# DoDecaCharlieCylon.net
KiCad netlist of a schematic drawn in EAGLE
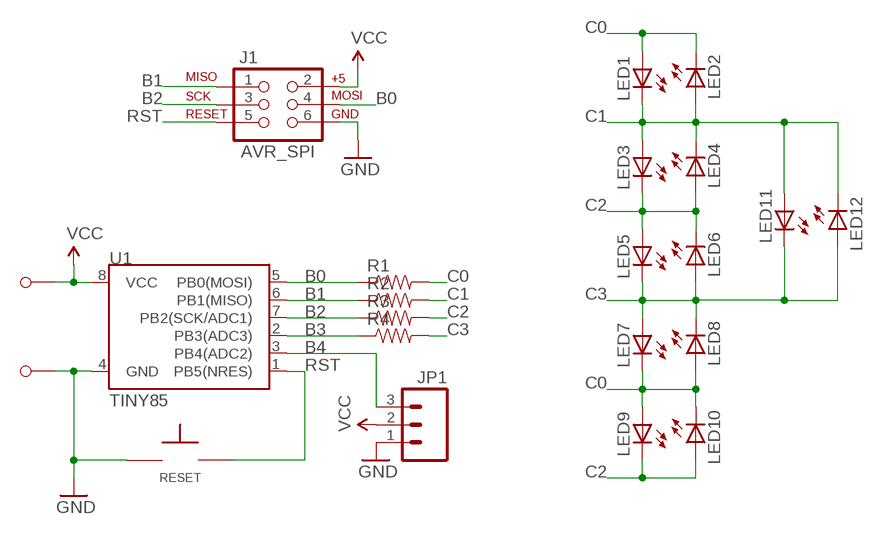
[diagram p0: schematic, sheet 1]

(export (version "E")
  (design (tool "Eeschema 10.0.6"))
  (components
    (comp (ref "J1")
      (value "AVR_SPI")
      (footprint "eagle-import:2X3-NS")
      (libsource (lib "eagle-import") (part "AVR_SPI_PRG_6LABELED"))
    )
    (comp (ref "JP1")
      (value "M03PTH")
      (footprint "eagle-import:1X03")
      (libsource (lib "eagle-import") (part "M03PTH"))
    )
    (comp (ref "LED1")
      (value "LEDOVAL")
      (footprint "eagle-import:LED-OVAL")
      (libsource (lib "eagle-import") (part "LEDOVAL"))
    )
    (comp (ref "LED2")
      (value "LEDOVAL")
      (footprint "eagle-import:LED-OVAL")
      (libsource (lib "eagle-import") (part "LEDOVAL"))
    )
    (comp (ref "LED3")
      (value "LEDOVAL")
      (footprint "eagle-import:LED-OVAL")
      (libsource (lib "eagle-import") (part "LEDOVAL"))
    )
    (comp (ref "LED4")
      (value "LEDOVAL")
      (footprint "eagle-import:LED-OVAL")
      (libsource (lib "eagle-import") (part "LEDOVAL"))
    )
    (comp (ref "LED5")
      (value "LEDOVAL")
      (footprint "eagle-import:LED-OVAL")
      (libsource (lib "eagle-import") (part "LEDOVAL"))
    )
    (comp (ref "LED6")
      (value "LEDOVAL")
      (footprint "eagle-import:LED-OVAL")
      (libsource (lib "eagle-import") (part "LEDOVAL"))
    )
    (comp (ref "LED7")
      (value "LEDOVAL")
      (footprint "eagle-import:LED-OVAL")
      (libsource (lib "eagle-import") (part "LEDOVAL"))
    )
    (comp (ref "LED8")
      (value "LEDOVAL")
      (footprint "eagle-import:LED-OVAL")
      (libsource (lib "eagle-import") (part "LEDOVAL"))
    )
    (comp (ref "LED9")
      (value "LEDOVAL")
      (footprint "eagle-import:LED-OVAL")
      (libsource (lib "eagle-import") (part "LEDOVAL"))
    )
    (comp (ref "LED10")
      (value "LEDOVAL")
      (footprint "eagle-import:LED-OVAL")
      (libsource (lib "eagle-import") (part "LEDOVAL"))
    )
    (comp (ref "LED11")
      (value "LEDOVAL")
      (footprint "eagle-import:LED-OVAL")
      (libsource (lib "eagle-import") (part "LEDOVAL"))
    )
    (comp (ref "LED12")
      (value "LEDOVAL")
      (footprint "eagle-import:LED-OVAL")
      (libsource (lib "eagle-import") (part "LEDOVAL"))
    )
    (comp (ref "R1")
      (value "RESISTORAXIAL-0.3")
      (footprint "eagle-import:AXIAL-0.3")
      (libsource (lib "eagle-import") (part "RESISTORAXIAL-0.3"))
    )
    (comp (ref "R2")
      (value "RESISTORAXIAL-0.3")
      (footprint "eagle-import:AXIAL-0.3")
      (libsource (lib "eagle-import") (part "RESISTORAXIAL-0.3"))
    )
    (comp (ref "R3")
      (value "RESISTORAXIAL-0.3")
      (footprint "eagle-import:AXIAL-0.3")
      (libsource (lib "eagle-import") (part "RESISTORAXIAL-0.3"))
    )
    (comp (ref "R4")
      (value "RESISTORAXIAL-0.3")
      (footprint "eagle-import:AXIAL-0.3")
      (libsource (lib "eagle-import") (part "RESISTORAXIAL-0.3"))
    )
    (comp (ref "RESET")
      (value "TAC_SPST_NO")
      (footprint "eagle-import:TAC_SPST_NO")
      (libsource (lib "eagle-import") (part "TAC_SPST_NO"))
    )
    (comp (ref "U$1")
      (value "M1")
      (footprint "eagle-import:M1_NO_STRAIN")
      (libsource (lib "eagle-import") (part "M1"))
    )
    (comp (ref "U$2")
      (value "M1")
      (footprint "eagle-import:M1_NO_STRAIN")
      (libsource (lib "eagle-import") (part "M1"))
    )
    (comp (ref "U1")
      (value "TINY85")
      (footprint "eagle-import:DIP08")
      (libsource (lib "eagle-import") (part "ATTINY45TINY85-20-DIP"))
    )
  )
  (nets
    (net (code "1") (name "/B0") (class "Default")
      (node (ref "J1") (pin "4") (pinfunction "MOSI_4") (pintype "passive"))
      (node (ref "R1") (pin "P$1") (pinfunction "1_P$1") (pintype "passive"))
      (node (ref "U1") (pin "5") (pinfunction "PB0(MOSI)_5") (pintype "bidirectional"))
    )
    (net (code "2") (name "/B1") (class "Default")
      (node (ref "J1") (pin "1") (pinfunction "MISO_1") (pintype "passive"))
      (node (ref "R2") (pin "P$1") (pinfunction "1_P$1") (pintype "passive"))
      (node (ref "U1") (pin "6") (pinfunction "PB1(MISO)_6") (pintype "bidirectional"))
    )
    (net (code "3") (name "/B2") (class "Default")
      (node (ref "J1") (pin "3") (pinfunction "SCK_3") (pintype "passive"))
      (node (ref "R3") (pin "P$1") (pinfunction "1_P$1") (pintype "passive"))
      (node (ref "U1") (pin "7") (pinfunction "PB2(SCK/ADC1)_7") (pintype "bidirectional"))
    )
    (net (code "4") (name "/B3") (class "Default")
      (node (ref "R4") (pin "P$1") (pinfunction "1_P$1") (pintype "passive"))
      (node (ref "U1") (pin "2") (pinfunction "PB3(ADC3)_2") (pintype "bidirectional"))
    )
    (net (code "5") (name "/B4") (class "Default")
      (node (ref "JP1") (pin "3") (pinfunction "3_3") (pintype "passive"))
      (node (ref "U1") (pin "3") (pinfunction "PB4(ADC2)_3") (pintype "bidirectional"))
    )
    (net (code "6") (name "/C0") (class "Default")
      (node (ref "LED1") (pin "ANODE") (pinfunction "A_ANODE") (pintype "passive"))
      (node (ref "LED10") (pin "CATHODE") (pinfunction "C_CATHODE") (pintype "passive"))
      (node (ref "LED2") (pin "CATHODE") (pinfunction "C_CATHODE") (pintype "passive"))
      (node (ref "LED7") (pin "CATHODE") (pinfunction "C_CATHODE") (pintype "passive"))
      (node (ref "LED8") (pin "ANODE") (pinfunction "A_ANODE") (pintype "passive"))
      (node (ref "LED9") (pin "ANODE") (pinfunction "A_ANODE") (pintype "passive"))
      (node (ref "R1") (pin "P$2") (pinfunction "2_P$2") (pintype "passive"))
    )
    (net (code "7") (name "/C1") (class "Default")
      (node (ref "LED1") (pin "CATHODE") (pinfunction "C_CATHODE") (pintype "passive"))
      (node (ref "LED11") (pin "ANODE") (pinfunction "A_ANODE") (pintype "passive"))
      (node (ref "LED12") (pin "CATHODE") (pinfunction "C_CATHODE") (pintype "passive"))
      (node (ref "LED2") (pin "ANODE") (pinfunction "A_ANODE") (pintype "passive"))
      (node (ref "LED3") (pin "ANODE") (pinfunction "A_ANODE") (pintype "passive"))
      (node (ref "LED4") (pin "CATHODE") (pinfunction "C_CATHODE") (pintype "passive"))
      (node (ref "R2") (pin "P$2") (pinfunction "2_P$2") (pintype "passive"))
    )
    (net (code "8") (name "/C2") (class "Default")
      (node (ref "LED10") (pin "ANODE") (pinfunction "A_ANODE") (pintype "passive"))
      (node (ref "LED3") (pin "CATHODE") (pinfunction "C_CATHODE") (pintype "passive"))
      (node (ref "LED4") (pin "ANODE") (pinfunction "A_ANODE") (pintype "passive"))
      (node (ref "LED5") (pin "ANODE") (pinfunction "A_ANODE") (pintype "passive"))
      (node (ref "LED6") (pin "CATHODE") (pinfunction "C_CATHODE") (pintype "passive"))
      (node (ref "LED9") (pin "CATHODE") (pinfunction "C_CATHODE") (pintype "passive"))
      (node (ref "R3") (pin "P$2") (pinfunction "2_P$2") (pintype "passive"))
    )
    (net (code "9") (name "/C3") (class "Default")
      (node (ref "LED11") (pin "CATHODE") (pinfunction "C_CATHODE") (pintype "passive"))
      (node (ref "LED12") (pin "ANODE") (pinfunction "A_ANODE") (pintype "passive"))
      (node (ref "LED5") (pin "CATHODE") (pinfunction "C_CATHODE") (pintype "passive"))
      (node (ref "LED6") (pin "ANODE") (pinfunction "A_ANODE") (pintype "passive"))
      (node (ref "LED7") (pin "ANODE") (pinfunction "A_ANODE") (pintype "passive"))
      (node (ref "LED8") (pin "CATHODE") (pinfunction "C_CATHODE") (pintype "passive"))
      (node (ref "R4") (pin "P$2") (pinfunction "2_P$2") (pintype "passive"))
    )
    (net (code "10") (name "/RST") (class "Default")
      (node (ref "J1") (pin "5") (pinfunction "RST_5") (pintype "passive"))
      (node (ref "RESET") (pin "P$2") (pinfunction "P$2_P$2") (pintype "bidirectional"))
      (node (ref "U1") (pin "1") (pinfunction "PB5(NRES)_1") (pintype "bidirectional"))
    )
    (net (code "11") (name "GND") (class "Default")
      (node (ref "J1") (pin "6") (pinfunction "GND_6") (pintype "passive"))
      (node (ref "JP1") (pin "1") (pinfunction "1_1") (pintype "passive"))
      (node (ref "RESET") (pin "P$1") (pinfunction "P$1_P$1") (pintype "bidirectional"))
      (node (ref "U$2") (pin "P$1") (pinfunction "P$1_P$1") (pintype "bidirectional"))
      (node (ref "U1") (pin "4") (pinfunction "GND_4") (pintype "bidirectional"))
    )
    (net (code "12") (name "VCC") (class "Default")
      (node (ref "J1") (pin "2") (pinfunction "V+_2") (pintype "passive"))
      (node (ref "JP1") (pin "2") (pinfunction "2_2") (pintype "passive"))
      (node (ref "U$1") (pin "P$1") (pinfunction "P$1_P$1") (pintype "bidirectional"))
      (node (ref "U1") (pin "8") (pinfunction "VCC_8") (pintype "bidirectional"))
    )
  )
)
